# phoboardv1.net
KiCad netlist of a schematic drawn in EAGLE
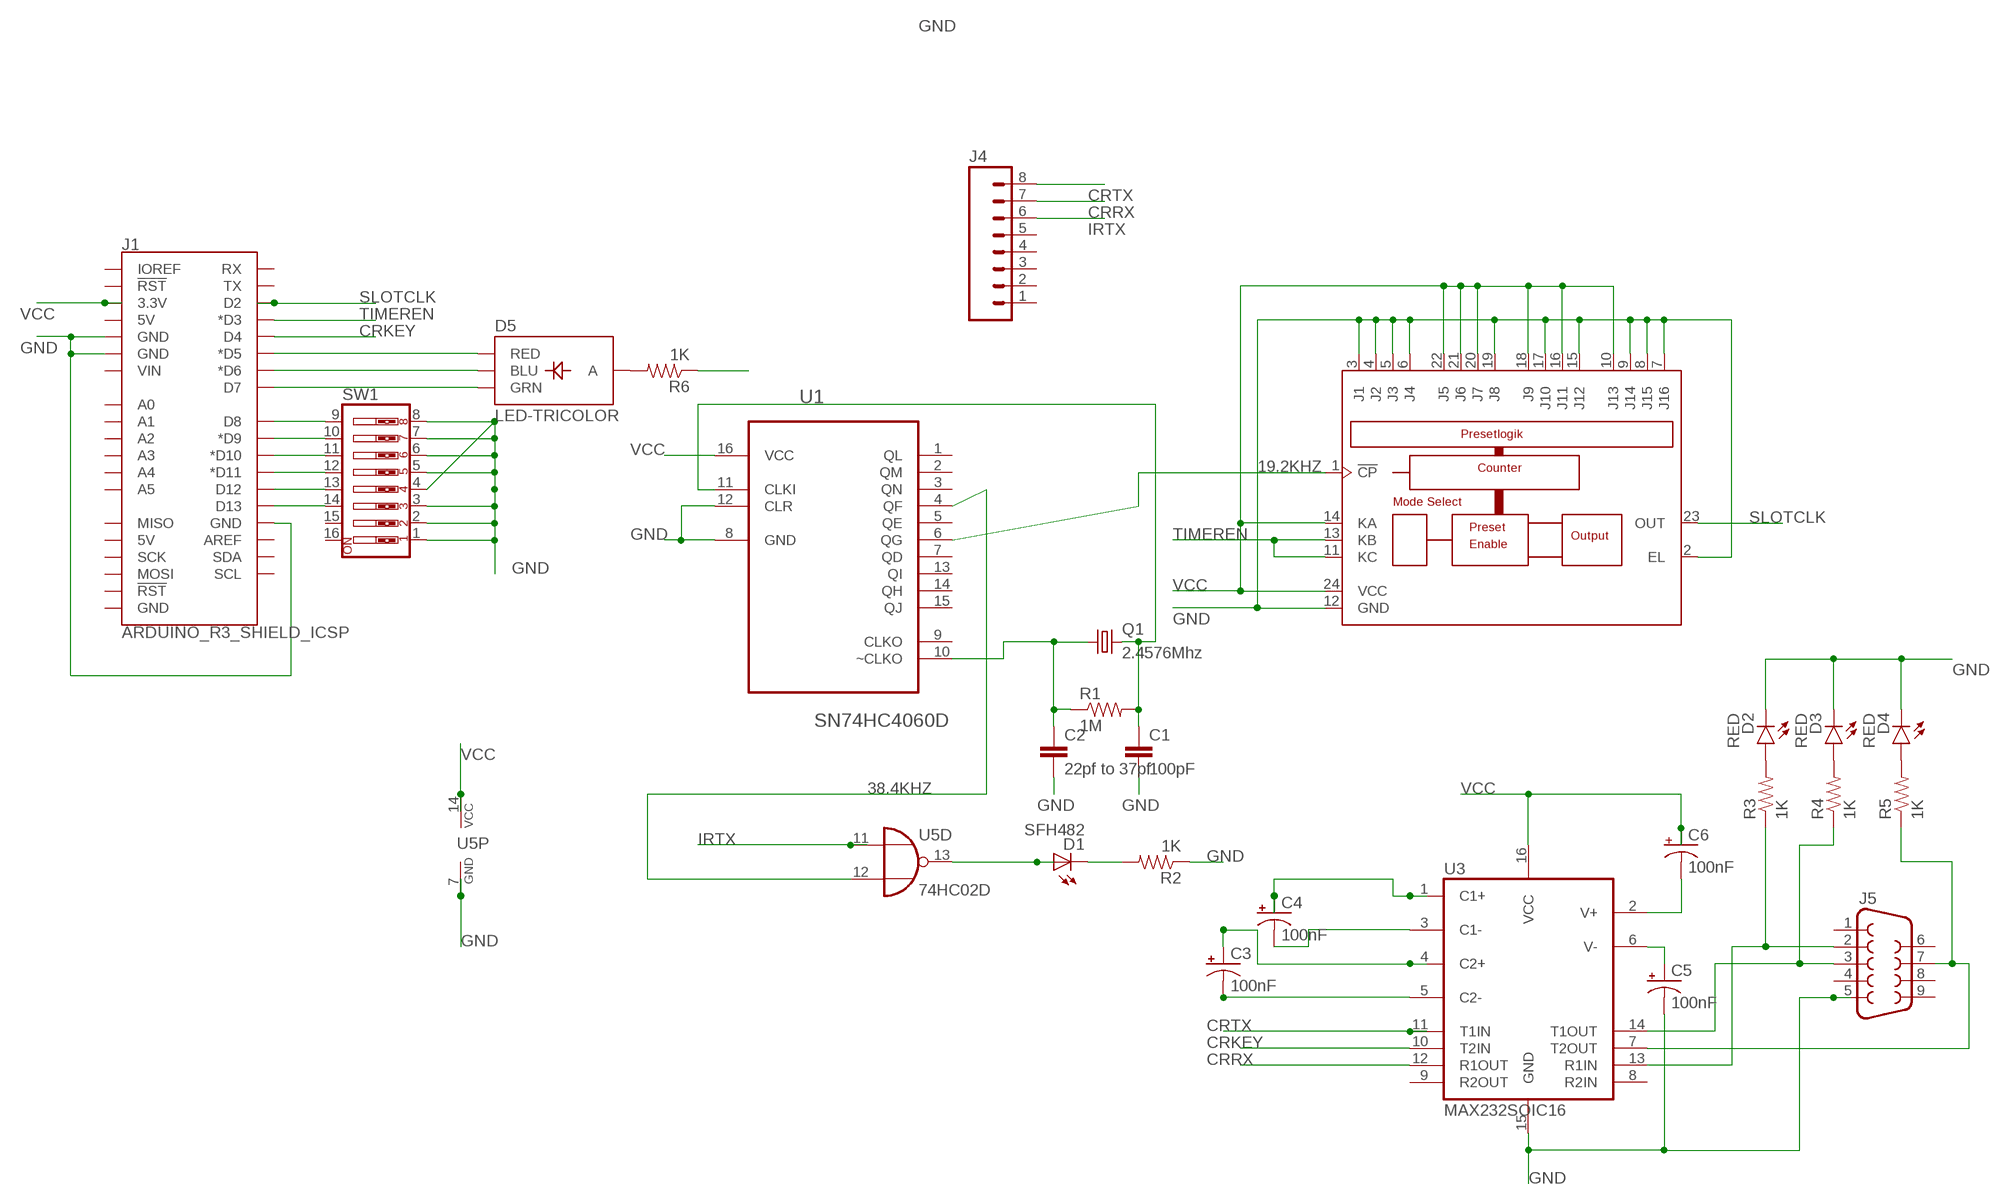
[diagram p0: schematic, sheet 1]

(export (version "E")
  (design (tool "Eeschema 10.0.6"))
  (components
    (comp (ref "C1")
      (value "100pF")
      (footprint "eagle-import:CAP-PTH-SMALL-KIT")
      (libsource (lib "eagle-import") (part "0.1UF-50V-20%(PTH)KIT-EZ"))
    )
    (comp (ref "C2")
      (value "22pf to 37pf")
      (footprint "eagle-import:CAP-PTH-SMALL-KIT")
      (libsource (lib "eagle-import") (part "0.1UF-50V-20%(PTH)KIT-EZ"))
    )
    (comp (ref "C3")
      (value "100nF")
      (footprint "eagle-import:EIA3216")
      (libsource (lib "eagle-import") (part "CAP_POL1206"))
    )
    (comp (ref "C4")
      (value "100nF")
      (footprint "eagle-import:EIA3216")
      (libsource (lib "eagle-import") (part "CAP_POL1206"))
    )
    (comp (ref "C5")
      (value "100nF")
      (footprint "eagle-import:EIA3216")
      (libsource (lib "eagle-import") (part "CAP_POL1206"))
    )
    (comp (ref "C6")
      (value "100nF")
      (footprint "eagle-import:EIA3216")
      (libsource (lib "eagle-import") (part "CAP_POL1206"))
    )
    (comp (ref "D1")
      (value "SFH482")
      (footprint "eagle-import:SFH482")
      (libsource (lib "eagle-import") (part "SFH482"))
    )
    (comp (ref "D2")
      (value "RED")
      (footprint "eagle-import:LED-0603")
      (libsource (lib "eagle-import") (part "LED-RED0603"))
    )
    (comp (ref "D3")
      (value "RED")
      (footprint "eagle-import:LED-0603")
      (libsource (lib "eagle-import") (part "LED-RED0603"))
    )
    (comp (ref "D4")
      (value "RED")
      (footprint "eagle-import:LED-0603")
      (libsource (lib "eagle-import") (part "LED-RED0603"))
    )
    (comp (ref "D5")
      (value "LED-TRICOLOR")
      (footprint "eagle-import:LED-TRICOLOR-SMD")
      (libsource (lib "eagle-import") (part "LED-TRICOLOR"))
    )
    (comp (ref "J1")
      (value "ARDUINO_R3_SHIELD_ICSP")
      (footprint "eagle-import:UNO_R3_SHIELD_ICSP")
      (libsource (lib "eagle-import") (part "ARDUINO_R3_SHIELD_ICSP"))
    )
    (comp (ref "J4")
      (value "M08")
      (footprint "eagle-import:1X08_ROUND")
      (libsource (lib "eagle-import") (part "M08"))
    )
    (comp (ref "J5")
      (value "DB9MALE")
      (footprint "eagle-import:DB9_MALE")
      (libsource (lib "eagle-import") (part "DB9MALE"))
    )
    (comp (ref "Q1")
      (value "2.4576Mhz")
      (footprint "eagle-import:HC49U70")
      (libsource (lib "eagle-import") (part "CRYSTALHC49U70"))
    )
    (comp (ref "R1")
      (value "1M")
      (footprint "eagle-import:AXIAL-0.4")
      (libsource (lib "eagle-import") (part "RESISTORPTH-1/4W"))
    )
    (comp (ref "R2")
      (value "1K")
      (footprint "eagle-import:0603-RES")
      (libsource (lib "eagle-import") (part "1KOHM-1/10W-1%(0603)"))
    )
    (comp (ref "R3")
      (value "1K")
      (footprint "eagle-import:0603-RES")
      (libsource (lib "eagle-import") (part "1KOHM-1/10W-1%(0603)"))
    )
    (comp (ref "R4")
      (value "1K")
      (footprint "eagle-import:0603-RES")
      (libsource (lib "eagle-import") (part "1KOHM-1/10W-1%(0603)"))
    )
    (comp (ref "R5")
      (value "1K")
      (footprint "eagle-import:0603-RES")
      (libsource (lib "eagle-import") (part "1KOHM-1/10W-1%(0603)"))
    )
    (comp (ref "R6")
      (value "1K")
      (footprint "eagle-import:0603-RES")
      (libsource (lib "eagle-import") (part "1KOHM-1/10W-1%(0603)"))
    )
    (comp (ref "SW1")
      (value "SW_DIP-8")
      (footprint "eagle-import:DIPSWITCH-08")
      (libsource (lib "eagle-import") (part "SW_DIP-8"))
    )
    (comp (ref "U1")
      (value "SN74HC4060D")
      (footprint "eagle-import:SOIC127P600X175-16N")
      (libsource (lib "eagle-import") (part "SN74HC4060D"))
    )
    (comp (ref "U2")
      (value "74HC59D")
      (footprint "eagle-import:SO24W")
      (libsource (lib "eagle-import") (part "7459DHC"))
    )
    (comp (ref "U3")
      (value "MAX232SOIC16")
      (footprint "eagle-import:SO016")
      (libsource (lib "eagle-import") (part "MAX232SOIC16"))
    )
    (comp (ref "U5")
      (value "74HC02D")
      (footprint "eagle-import:SO14")
      (libsource (lib "eagle-import") (part "7402DHC"))
    )
  )
  (nets
    (net (code "1") (name "/19.2KHZ") (class "Default")
      (node (ref "U1") (pin "6") (pinfunction "QG_6") (pintype "output"))
      (node (ref "U2") (pin "1") (pinfunction "~{CP}_1") (pintype "input"))
    )
    (net (code "2") (name "/38.4KHZ") (class "Default")
      (node (ref "U1") (pin "4") (pinfunction "QF_4") (pintype "output"))
      (node (ref "U5") (pin "12") (pinfunction "I1_12") (pintype "input"))
    )
    (net (code "3") (name "/CRKEY") (class "Default")
      (node (ref "J1") (pin "D4") (pinfunction "D4_D4") (pintype "bidirectional"))
      (node (ref "U3") (pin "10") (pinfunction "T2IN_10") (pintype "input"))
    )
    (net (code "4") (name "/CRRX") (class "Default")
      (node (ref "J4") (pin "7") (pinfunction "7_7") (pintype "passive"))
      (node (ref "U3") (pin "12") (pinfunction "R1OUT_12") (pintype "output"))
    )
    (net (code "5") (name "/CRTX") (class "Default")
      (node (ref "J4") (pin "8") (pinfunction "8_8") (pintype "passive"))
      (node (ref "U3") (pin "11") (pinfunction "T1IN_11") (pintype "input"))
    )
    (net (code "6") (name "/GND") (class "Default")
      (node (ref "C1") (pin "2") (pinfunction "2_2") (pintype "passive"))
      (node (ref "C2") (pin "2") (pinfunction "2_2") (pintype "passive"))
      (node (ref "C5") (pin "C") (pinfunction "-_C") (pintype "passive"))
      (node (ref "D2") (pin "C") (pinfunction "C_C") (pintype "passive"))
      (node (ref "D3") (pin "C") (pinfunction "C_C") (pintype "passive"))
      (node (ref "D4") (pin "C") (pinfunction "C_C") (pintype "passive"))
      (node (ref "J1") (pin "GND@0") (pinfunction "GND_GND@0") (pintype "bidirectional"))
      (node (ref "J1") (pin "GND@1") (pinfunction "GND_GND@1") (pintype "bidirectional"))
      (node (ref "J1") (pin "GND@2") (pinfunction "GND_GND@2") (pintype "bidirectional"))
      (node (ref "J5") (pin "5") (pinfunction "5_5") (pintype "passive"))
      (node (ref "R2") (pin "1") (pinfunction "1_1") (pintype "passive"))
      (node (ref "R6") (pin "1") (pinfunction "1_1") (pintype "passive"))
      (node (ref "SW1") (pin "1") (pinfunction "1_1") (pintype "passive"))
      (node (ref "SW1") (pin "2") (pinfunction "2_2") (pintype "passive"))
      (node (ref "SW1") (pin "3") (pinfunction "3_3") (pintype "passive"))
      (node (ref "SW1") (pin "4") (pinfunction "4_4") (pintype "passive"))
      (node (ref "SW1") (pin "5") (pinfunction "5_5") (pintype "passive"))
      (node (ref "SW1") (pin "6") (pinfunction "6_6") (pintype "passive"))
      (node (ref "SW1") (pin "7") (pinfunction "7_7") (pintype "passive"))
      (node (ref "SW1") (pin "8") (pinfunction "8_8") (pintype "passive"))
      (node (ref "U1") (pin "12") (pinfunction "CLR_12") (pintype "input"))
      (node (ref "U1") (pin "8") (pinfunction "GND_8") (pintype "passive"))
      (node (ref "U2") (pin "12") (pinfunction "GND_12") (pintype "power_in"))
      (node (ref "U2") (pin "15") (pinfunction "J12_15") (pintype "input"))
      (node (ref "U2") (pin "17") (pinfunction "J10_17") (pintype "input"))
      (node (ref "U2") (pin "19") (pinfunction "J8_19") (pintype "input"))
      (node (ref "U2") (pin "2") (pinfunction "EL_2") (pintype "input"))
      (node (ref "U2") (pin "3") (pinfunction "J1_3") (pintype "input"))
      (node (ref "U2") (pin "4") (pinfunction "J2_4") (pintype "input"))
      (node (ref "U2") (pin "5") (pinfunction "J3_5") (pintype "input"))
      (node (ref "U2") (pin "6") (pinfunction "J4_6") (pintype "input"))
      (node (ref "U2") (pin "7") (pinfunction "J16_7") (pintype "input"))
      (node (ref "U2") (pin "8") (pinfunction "J15_8") (pintype "input"))
      (node (ref "U2") (pin "9") (pinfunction "J14_9") (pintype "input"))
      (node (ref "U3") (pin "15") (pinfunction "GND_15") (pintype "bidirectional"))
      (node (ref "U5") (pin "7") (pinfunction "GND_7") (pintype "power_in"))
    )
    (net (code "7") (name "/IRTX") (class "Default")
      (node (ref "J4") (pin "6") (pinfunction "6_6") (pintype "passive"))
      (node (ref "U5") (pin "11") (pinfunction "I0_11") (pintype "input"))
    )
    (net (code "8") (name "/SLOTCLK") (class "Default")
      (node (ref "J1") (pin "D2") (pinfunction "D2_D2") (pintype "bidirectional"))
      (node (ref "U2") (pin "23") (pinfunction "OUT_23") (pintype "output"))
    )
    (net (code "9") (name "/TIMEREN") (class "Default")
      (node (ref "J1") (pin "D3") (pinfunction "*D3_D3") (pintype "bidirectional"))
      (node (ref "U2") (pin "11") (pinfunction "KC_11") (pintype "input"))
      (node (ref "U2") (pin "13") (pinfunction "KB_13") (pintype "input"))
    )
    (net (code "10") (name "/VCC") (class "Default")
      (node (ref "C6") (pin "A") (pinfunction "+_A") (pintype "passive"))
      (node (ref "J1") (pin "3.3V") (pinfunction "3.3V_3.3V") (pintype "bidirectional"))
      (node (ref "U1") (pin "16") (pinfunction "VCC_16") (pintype "power_in"))
      (node (ref "U2") (pin "10") (pinfunction "J13_10") (pintype "input"))
      (node (ref "U2") (pin "14") (pinfunction "KA_14") (pintype "input"))
      (node (ref "U2") (pin "16") (pinfunction "J11_16") (pintype "input"))
      (node (ref "U2") (pin "18") (pinfunction "J9_18") (pintype "input"))
      (node (ref "U2") (pin "20") (pinfunction "J7_20") (pintype "input"))
      (node (ref "U2") (pin "21") (pinfunction "J6_21") (pintype "input"))
      (node (ref "U2") (pin "22") (pinfunction "J5_22") (pintype "input"))
      (node (ref "U2") (pin "24") (pinfunction "VCC_24") (pintype "power_in"))
      (node (ref "U3") (pin "16") (pinfunction "VCC_16") (pintype "bidirectional"))
      (node (ref "U5") (pin "14") (pinfunction "VCC_14") (pintype "power_in"))
    )
    (net (code "11") (name "Net-(C3-+)") (class "Default")
      (node (ref "C3") (pin "A") (pinfunction "+_A") (pintype "passive"))
      (node (ref "U3") (pin "4") (pinfunction "C2+_4") (pintype "bidirectional"))
    )
    (net (code "12") (name "Net-(C3--)") (class "Default")
      (node (ref "C3") (pin "C") (pinfunction "-_C") (pintype "passive"))
      (node (ref "U3") (pin "5") (pinfunction "C2-_5") (pintype "bidirectional"))
    )
    (net (code "13") (name "Net-(C4-+)") (class "Default")
      (node (ref "C4") (pin "A") (pinfunction "+_A") (pintype "passive"))
      (node (ref "U3") (pin "1") (pinfunction "C1+_1") (pintype "bidirectional"))
    )
    (net (code "14") (name "Net-(C4--)") (class "Default")
      (node (ref "C4") (pin "C") (pinfunction "-_C") (pintype "passive"))
      (node (ref "U3") (pin "3") (pinfunction "C1-_3") (pintype "bidirectional"))
    )
    (net (code "15") (name "Net-(C5-+)") (class "Default")
      (node (ref "C5") (pin "A") (pinfunction "+_A") (pintype "passive"))
      (node (ref "U3") (pin "6") (pinfunction "V-_6") (pintype "bidirectional"))
    )
    (net (code "16") (name "Net-(C6--)") (class "Default")
      (node (ref "C6") (pin "C") (pinfunction "-_C") (pintype "passive"))
      (node (ref "U3") (pin "2") (pinfunction "V+_2") (pintype "bidirectional"))
    )
    (net (code "17") (name "Net-(D1-C)") (class "Default")
      (node (ref "D1") (pin "K") (pinfunction "C_K") (pintype "passive"))
      (node (ref "R2") (pin "2") (pinfunction "2_2") (pintype "passive"))
    )
    (net (code "18") (name "Net-(D2-PadA)") (class "Default")
      (node (ref "D2") (pin "A") (pinfunction "A_A") (pintype "passive"))
      (node (ref "R3") (pin "2") (pinfunction "2_2") (pintype "passive"))
    )
    (net (code "19") (name "Net-(D3-PadA)") (class "Default")
      (node (ref "D3") (pin "A") (pinfunction "A_A") (pintype "passive"))
      (node (ref "R4") (pin "2") (pinfunction "2_2") (pintype "passive"))
    )
    (net (code "20") (name "Net-(D4-PadA)") (class "Default")
      (node (ref "D4") (pin "A") (pinfunction "A_A") (pintype "passive"))
      (node (ref "R5") (pin "2") (pinfunction "2_2") (pintype "passive"))
    )
    (net (code "21") (name "Net-(D5-BLU)") (class "Default")
      (node (ref "D5") (pin "B") (pinfunction "BLU_B") (pintype "bidirectional"))
      (node (ref "J1") (pin "D6") (pinfunction "*D6_D6") (pintype "bidirectional"))
    )
    (net (code "22") (name "Net-(D5-GRN)") (class "Default")
      (node (ref "D5") (pin "G") (pinfunction "GRN_G") (pintype "bidirectional"))
      (node (ref "J1") (pin "D7") (pinfunction "D7_D7") (pintype "bidirectional"))
    )
    (net (code "23") (name "Net-(D5-PadA)") (class "Default")
      (node (ref "D5") (pin "A") (pinfunction "A_A") (pintype "bidirectional"))
      (node (ref "R6") (pin "2") (pinfunction "2_2") (pintype "passive"))
    )
    (net (code "24") (name "Net-(D5-RED)") (class "Default")
      (node (ref "D5") (pin "R") (pinfunction "RED_R") (pintype "bidirectional"))
      (node (ref "J1") (pin "D5") (pinfunction "*D5_D5") (pintype "bidirectional"))
    )
    (net (code "25") (name "Net-(J1-*D9)") (class "Default")
      (node (ref "J1") (pin "D9") (pinfunction "*D9_D9") (pintype "bidirectional"))
      (node (ref "SW1") (pin "10") (pinfunction "10_10") (pintype "passive"))
    )
    (net (code "26") (name "Net-(J1-*D10)") (class "Default")
      (node (ref "J1") (pin "D10") (pinfunction "*D10_D10") (pintype "bidirectional"))
      (node (ref "SW1") (pin "11") (pinfunction "11_11") (pintype "passive"))
    )
    (net (code "27") (name "Net-(J1-*D11)") (class "Default")
      (node (ref "J1") (pin "D11") (pinfunction "*D11_D11") (pintype "bidirectional"))
      (node (ref "SW1") (pin "12") (pinfunction "12_12") (pintype "passive"))
    )
    (net (code "28") (name "Net-(J1-PadD8)") (class "Default")
      (node (ref "J1") (pin "D8") (pinfunction "D8_D8") (pintype "bidirectional"))
      (node (ref "SW1") (pin "9") (pinfunction "9_9") (pintype "passive"))
    )
    (net (code "29") (name "Net-(J1-PadD12)") (class "Default")
      (node (ref "J1") (pin "D12") (pinfunction "D12_D12") (pintype "bidirectional"))
      (node (ref "SW1") (pin "13") (pinfunction "13_13") (pintype "passive"))
    )
    (net (code "30") (name "Net-(J1-PadD13)") (class "Default")
      (node (ref "J1") (pin "D13") (pinfunction "D13_D13") (pintype "bidirectional"))
      (node (ref "SW1") (pin "14") (pinfunction "14_14") (pintype "passive"))
    )
    (net (code "31") (name "Net-(R1-1)") (class "Default")
      (node (ref "C2") (pin "1") (pinfunction "1_1") (pintype "passive"))
      (node (ref "Q1") (pin "1") (pinfunction "1_1") (pintype "passive"))
      (node (ref "R1") (pin "P$1") (pinfunction "1_P$1") (pintype "passive"))
      (node (ref "U1") (pin "10") (pinfunction "~{CLKO}_10") (pintype "output"))
    )
    (net (code "32") (name "Net-(R1-2)") (class "Default")
      (node (ref "C1") (pin "1") (pinfunction "1_1") (pintype "passive"))
      (node (ref "Q1") (pin "2") (pinfunction "2_2") (pintype "passive"))
      (node (ref "R1") (pin "P$2") (pinfunction "2_P$2") (pintype "passive"))
      (node (ref "U1") (pin "11") (pinfunction "CLKI_11") (pintype "input"))
    )
    (net (code "33") (name "Net-(U3-R1IN)") (class "Default")
      (node (ref "J5") (pin "2") (pinfunction "2_2") (pintype "passive"))
      (node (ref "R3") (pin "1") (pinfunction "1_1") (pintype "passive"))
      (node (ref "U3") (pin "13") (pinfunction "R1IN_13") (pintype "input"))
    )
    (net (code "34") (name "Net-(U3-T1OUT)") (class "Default")
      (node (ref "J5") (pin "3") (pinfunction "3_3") (pintype "passive"))
      (node (ref "R4") (pin "1") (pinfunction "1_1") (pintype "passive"))
      (node (ref "U3") (pin "14") (pinfunction "T1OUT_14") (pintype "output"))
    )
    (net (code "35") (name "Net-(U3-T2OUT)") (class "Default")
      (node (ref "J5") (pin "7") (pinfunction "7_7") (pintype "passive"))
      (node (ref "R5") (pin "1") (pinfunction "1_1") (pintype "passive"))
      (node (ref "U3") (pin "7") (pinfunction "T2OUT_7") (pintype "output"))
    )
    (net (code "36") (name "Net-(U5D-O)") (class "Default")
      (node (ref "D1") (pin "A") (pinfunction "A_A") (pintype "passive"))
      (node (ref "U5") (pin "13") (pinfunction "O_13") (pintype "output"))
    )
    (net (code "37") (name "unconnected-(J1-5V-Pad5V_ICSP)") (class "Default")
      (node (ref "J1") (pin "5V_ICSP") (pinfunction "5V_5V_ICSP") (pintype "bidirectional"))
    )
    (net (code "38") (name "unconnected-(J1-GND-PadGND_ICSP)") (class "Default")
      (node (ref "J1") (pin "GND_ICSP") (pinfunction "GND_GND_ICSP") (pintype "bidirectional"))
    )
    (net (code "39") (name "unconnected-(J1-Pad5V)") (class "Default")
      (node (ref "J1") (pin "5V") (pinfunction "5V_5V") (pintype "bidirectional"))
    )
    (net (code "40") (name "unconnected-(J1-PadA0)") (class "Default")
      (node (ref "J1") (pin "A0") (pinfunction "A0_A0") (pintype "bidirectional"))
    )
    (net (code "41") (name "unconnected-(J1-PadA1)") (class "Default")
      (node (ref "J1") (pin "A1") (pinfunction "A1_A1") (pintype "bidirectional"))
    )
    (net (code "42") (name "unconnected-(J1-PadA2)") (class "Default")
      (node (ref "J1") (pin "A2") (pinfunction "A2_A2") (pintype "bidirectional"))
    )
    (net (code "43") (name "unconnected-(J1-PadA3)") (class "Default")
      (node (ref "J1") (pin "A3") (pinfunction "A3_A3") (pintype "bidirectional"))
    )
    (net (code "44") (name "unconnected-(J1-PadA4)") (class "Default")
      (node (ref "J1") (pin "A4") (pinfunction "A4_A4") (pintype "bidirectional"))
    )
    (net (code "45") (name "unconnected-(J1-PadA5)") (class "Default")
      (node (ref "J1") (pin "A5") (pinfunction "A5_A5") (pintype "bidirectional"))
    )
    (net (code "46") (name "unconnected-(J1-PadAREF)") (class "Default")
      (node (ref "J1") (pin "AREF") (pinfunction "AREF_AREF") (pintype "bidirectional"))
    )
    (net (code "47") (name "unconnected-(J1-PadIOREF)") (class "Default")
      (node (ref "J1") (pin "IOREF") (pinfunction "IOREF_IOREF") (pintype "bidirectional"))
    )
    (net (code "48") (name "unconnected-(J1-PadMISO)") (class "Default")
      (node (ref "J1") (pin "MISO") (pinfunction "MISO_MISO") (pintype "bidirectional"))
    )
    (net (code "49") (name "unconnected-(J1-PadMOSI)") (class "Default")
      (node (ref "J1") (pin "MOSI") (pinfunction "MOSI_MOSI") (pintype "bidirectional"))
    )
    (net (code "50") (name "unconnected-(J1-PadRX)") (class "Default")
      (node (ref "J1") (pin "RX") (pinfunction "RX_RX") (pintype "bidirectional"))
    )
    (net (code "51") (name "unconnected-(J1-PadSCK)") (class "Default")
      (node (ref "J1") (pin "SCK") (pinfunction "SCK_SCK") (pintype "bidirectional"))
    )
    (net (code "52") (name "unconnected-(J1-PadSCL)") (class "Default")
      (node (ref "J1") (pin "SCL") (pinfunction "SCL_SCL") (pintype "bidirectional"))
    )
    (net (code "53") (name "unconnected-(J1-PadSDA)") (class "Default")
      (node (ref "J1") (pin "SDA") (pinfunction "SDA_SDA") (pintype "bidirectional"))
    )
    (net (code "54") (name "unconnected-(J1-PadTX)") (class "Default")
      (node (ref "J1") (pin "TX") (pinfunction "TX_TX") (pintype "bidirectional"))
    )
    (net (code "55") (name "unconnected-(J1-PadVIN)") (class "Default")
      (node (ref "J1") (pin "VIN") (pinfunction "VIN_VIN") (pintype "bidirectional"))
    )
    (net (code "56") (name "unconnected-(J1-~{RST}-PadRES)") (class "Default")
      (node (ref "J1") (pin "RES") (pinfunction "~{RST}_RES") (pintype "bidirectional"))
    )
    (net (code "57") (name "unconnected-(J1-~{RST}-PadRST_ICSP)") (class "Default")
      (node (ref "J1") (pin "RST_ICSP") (pinfunction "~{RST}_RST_ICSP") (pintype "bidirectional"))
    )
    (net (code "58") (name "unconnected-(J4-Pad1)") (class "Default")
      (node (ref "J4") (pin "1") (pinfunction "1_1") (pintype "passive"))
    )
    (net (code "59") (name "unconnected-(J4-Pad2)") (class "Default")
      (node (ref "J4") (pin "2") (pinfunction "2_2") (pintype "passive"))
    )
    (net (code "60") (name "unconnected-(J4-Pad3)") (class "Default")
      (node (ref "J4") (pin "3") (pinfunction "3_3") (pintype "passive"))
    )
    (net (code "61") (name "unconnected-(J4-Pad4)") (class "Default")
      (node (ref "J4") (pin "4") (pinfunction "4_4") (pintype "passive"))
    )
    (net (code "62") (name "unconnected-(J4-Pad5)") (class "Default")
      (node (ref "J4") (pin "5") (pinfunction "5_5") (pintype "passive"))
    )
    (net (code "63") (name "unconnected-(J5-Pad1)") (class "Default")
      (node (ref "J5") (pin "1") (pinfunction "1_1") (pintype "passive"))
    )
    (net (code "64") (name "unconnected-(J5-Pad4)") (class "Default")
      (node (ref "J5") (pin "4") (pinfunction "4_4") (pintype "passive"))
    )
    (net (code "65") (name "unconnected-(J5-Pad6)") (class "Default")
      (node (ref "J5") (pin "6") (pinfunction "6_6") (pintype "passive"))
    )
    (net (code "66") (name "unconnected-(J5-Pad8)") (class "Default")
      (node (ref "J5") (pin "8") (pinfunction "8_8") (pintype "passive"))
    )
    (net (code "67") (name "unconnected-(J5-Pad9)") (class "Default")
      (node (ref "J5") (pin "9") (pinfunction "9_9") (pintype "passive"))
    )
    (net (code "68") (name "unconnected-(SW1-Pad15)") (class "Default")
      (node (ref "SW1") (pin "15") (pinfunction "15_15") (pintype "passive"))
    )
    (net (code "69") (name "unconnected-(SW1-Pad16)") (class "Default")
      (node (ref "SW1") (pin "16") (pinfunction "16_16") (pintype "passive"))
    )
    (net (code "70") (name "unconnected-(U1-CLKO-Pad9)") (class "Default")
      (node (ref "U1") (pin "9") (pinfunction "CLKO_9") (pintype "output"))
    )
    (net (code "71") (name "unconnected-(U1-QD-Pad7)") (class "Default")
      (node (ref "U1") (pin "7") (pinfunction "QD_7") (pintype "output"))
    )
    (net (code "72") (name "unconnected-(U1-QE-Pad5)") (class "Default")
      (node (ref "U1") (pin "5") (pinfunction "QE_5") (pintype "output"))
    )
    (net (code "73") (name "unconnected-(U1-QH-Pad14)") (class "Default")
      (node (ref "U1") (pin "14") (pinfunction "QH_14") (pintype "output"))
    )
    (net (code "74") (name "unconnected-(U1-QI-Pad13)") (class "Default")
      (node (ref "U1") (pin "13") (pinfunction "QI_13") (pintype "output"))
    )
    (net (code "75") (name "unconnected-(U1-QJ-Pad15)") (class "Default")
      (node (ref "U1") (pin "15") (pinfunction "QJ_15") (pintype "output"))
    )
    (net (code "76") (name "unconnected-(U1-QL-Pad1)") (class "Default")
      (node (ref "U1") (pin "1") (pinfunction "QL_1") (pintype "output"))
    )
    (net (code "77") (name "unconnected-(U1-QM-Pad2)") (class "Default")
      (node (ref "U1") (pin "2") (pinfunction "QM_2") (pintype "output"))
    )
    (net (code "78") (name "unconnected-(U1-QN-Pad3)") (class "Default")
      (node (ref "U1") (pin "3") (pinfunction "QN_3") (pintype "output"))
    )
    (net (code "79") (name "unconnected-(U3-R2IN-Pad8)") (class "Default")
      (node (ref "U3") (pin "8") (pinfunction "R2IN_8") (pintype "input"))
    )
    (net (code "80") (name "unconnected-(U3-R2OUT-Pad9)") (class "Default")
      (node (ref "U3") (pin "9") (pinfunction "R2OUT_9") (pintype "output"))
    )
  )
)
